# circuit.net
KiCad netlist of a schematic drawn in EAGLE
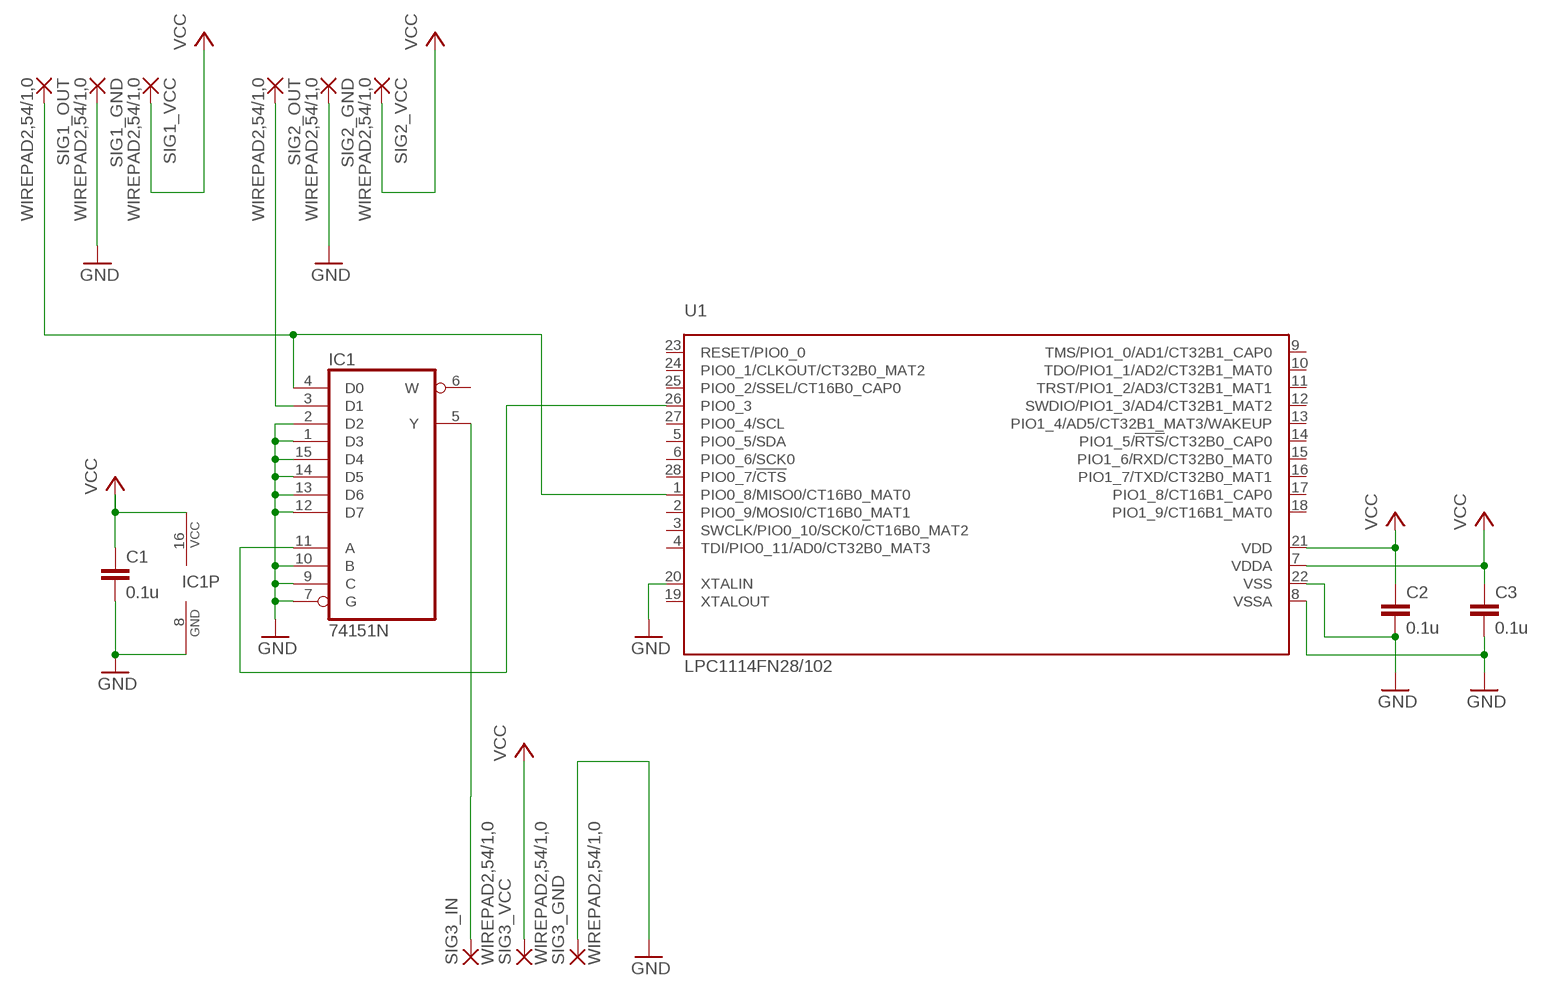
[diagram p0: schematic, sheet 1]

(export (version "E")
  (design (tool "Eeschema 10.0.6"))
  (components
    (comp (ref "C1")
      (value "0.1u")
      (footprint "eagle-import:C025-024X044")
      (libsource (lib "eagle-import") (part "C-EU025-024X044"))
    )
    (comp (ref "C2")
      (value "0.1u")
      (footprint "eagle-import:C025-024X044")
      (libsource (lib "eagle-import") (part "C-EU025-024X044"))
    )
    (comp (ref "C3")
      (value "0.1u")
      (footprint "eagle-import:C025-024X044")
      (libsource (lib "eagle-import") (part "C-EU025-024X044"))
    )
    (comp (ref "IC1")
      (value "74151N")
      (footprint "eagle-import:DIL16")
      (libsource (lib "eagle-import") (part "74151N"))
    )
    (comp (ref "SIG1_GND")
      (value "WIREPAD2,54/1,0")
      (footprint "eagle-import:2,54_1,0")
      (libsource (lib "eagle-import") (part "WIREPAD2,54/1,0"))
    )
    (comp (ref "SIG1_OUT")
      (value "WIREPAD2,54/1,0")
      (footprint "eagle-import:2,54_1,0")
      (libsource (lib "eagle-import") (part "WIREPAD2,54/1,0"))
    )
    (comp (ref "SIG1_VCC")
      (value "WIREPAD2,54/1,0")
      (footprint "eagle-import:2,54_1,0")
      (libsource (lib "eagle-import") (part "WIREPAD2,54/1,0"))
    )
    (comp (ref "SIG2_GND")
      (value "WIREPAD2,54/1,0")
      (footprint "eagle-import:2,54_1,0")
      (libsource (lib "eagle-import") (part "WIREPAD2,54/1,0"))
    )
    (comp (ref "SIG2_OUT")
      (value "WIREPAD2,54/1,0")
      (footprint "eagle-import:2,54_1,0")
      (libsource (lib "eagle-import") (part "WIREPAD2,54/1,0"))
    )
    (comp (ref "SIG2_VCC")
      (value "WIREPAD2,54/1,0")
      (footprint "eagle-import:2,54_1,0")
      (libsource (lib "eagle-import") (part "WIREPAD2,54/1,0"))
    )
    (comp (ref "SIG3_GND")
      (value "WIREPAD2,54/1,0")
      (footprint "eagle-import:2,54_1,0")
      (libsource (lib "eagle-import") (part "WIREPAD2,54/1,0"))
    )
    (comp (ref "SIG3_IN")
      (value "WIREPAD2,54/1,0")
      (footprint "eagle-import:2,54_1,0")
      (libsource (lib "eagle-import") (part "WIREPAD2,54/1,0"))
    )
    (comp (ref "SIG3_VCC")
      (value "WIREPAD2,54/1,0")
      (footprint "eagle-import:2,54_1,0")
      (libsource (lib "eagle-import") (part "WIREPAD2,54/1,0"))
    )
    (comp (ref "U1")
      (value "LPC1114FN28/102")
      (footprint "eagle-import:SOT117")
      (libsource (lib "eagle-import") (part "LPC1114FN28/102"))
    )
  )
  (nets
    (net (code "1") (name "GND") (class "Default")
      (node (ref "C1") (pin "2") (pinfunction "2_2") (pintype "passive"))
      (node (ref "C2") (pin "2") (pinfunction "2_2") (pintype "passive"))
      (node (ref "C3") (pin "2") (pinfunction "2_2") (pintype "passive"))
      (node (ref "IC1") (pin "1") (pinfunction "D3_1") (pintype "input"))
      (node (ref "IC1") (pin "10") (pinfunction "B_10") (pintype "input"))
      (node (ref "IC1") (pin "12") (pinfunction "D7_12") (pintype "input"))
      (node (ref "IC1") (pin "13") (pinfunction "D6_13") (pintype "input"))
      (node (ref "IC1") (pin "14") (pinfunction "D5_14") (pintype "input"))
      (node (ref "IC1") (pin "15") (pinfunction "D4_15") (pintype "input"))
      (node (ref "IC1") (pin "2") (pinfunction "D2_2") (pintype "input"))
      (node (ref "IC1") (pin "7") (pinfunction "G_7") (pintype "input"))
      (node (ref "IC1") (pin "8") (pinfunction "GND_8") (pintype "power_in"))
      (node (ref "IC1") (pin "9") (pinfunction "C_9") (pintype "input"))
      (node (ref "SIG1_GND") (pin "1") (pinfunction "P_1") (pintype "passive"))
      (node (ref "SIG2_GND") (pin "1") (pinfunction "P_1") (pintype "passive"))
      (node (ref "SIG3_GND") (pin "1") (pinfunction "P_1") (pintype "passive"))
      (node (ref "U1") (pin "20") (pinfunction "XTALIN_20") (pintype "input"))
      (node (ref "U1") (pin "22") (pinfunction "VSS_22") (pintype "power_in"))
      (node (ref "U1") (pin "8") (pinfunction "VSSA_8") (pintype "power_in"))
    )
    (net (code "2") (name "Net-(IC1A-A)") (class "Default")
      (node (ref "IC1") (pin "11") (pinfunction "A_11") (pintype "input"))
      (node (ref "U1") (pin "26") (pinfunction "PIO0_3_26") (pintype "bidirectional"))
    )
    (net (code "3") (name "Net-(IC1A-D0)") (class "Default")
      (node (ref "IC1") (pin "4") (pinfunction "D0_4") (pintype "input"))
      (node (ref "SIG1_OUT") (pin "1") (pinfunction "P_1") (pintype "passive"))
      (node (ref "U1") (pin "1") (pinfunction "PIO0_8/MISO0/CT16B0_MAT0_1") (pintype "bidirectional"))
    )
    (net (code "4") (name "Net-(IC1A-D1)") (class "Default")
      (node (ref "IC1") (pin "3") (pinfunction "D1_3") (pintype "input"))
      (node (ref "SIG2_OUT") (pin "1") (pinfunction "P_1") (pintype "passive"))
    )
    (net (code "5") (name "Net-(IC1A-Y)") (class "Default")
      (node (ref "IC1") (pin "5") (pinfunction "Y_5") (pintype "output"))
      (node (ref "SIG3_IN") (pin "1") (pinfunction "P_1") (pintype "passive"))
    )
    (net (code "6") (name "VCC") (class "Default")
      (node (ref "C1") (pin "1") (pinfunction "1_1") (pintype "passive"))
      (node (ref "C2") (pin "1") (pinfunction "1_1") (pintype "passive"))
      (node (ref "C3") (pin "1") (pinfunction "1_1") (pintype "passive"))
      (node (ref "IC1") (pin "16") (pinfunction "VCC_16") (pintype "power_in"))
      (node (ref "SIG1_VCC") (pin "1") (pinfunction "P_1") (pintype "passive"))
      (node (ref "SIG2_VCC") (pin "1") (pinfunction "P_1") (pintype "passive"))
      (node (ref "SIG3_VCC") (pin "1") (pinfunction "P_1") (pintype "passive"))
      (node (ref "U1") (pin "21") (pinfunction "VDD_21") (pintype "power_in"))
      (node (ref "U1") (pin "7") (pinfunction "VDDA_7") (pintype "power_in"))
    )
    (net (code "7") (name "unconnected-(IC1A-W-Pad6)") (class "Default")
      (node (ref "IC1") (pin "6") (pinfunction "W_6") (pintype "output"))
    )
    (net (code "8") (name "unconnected-(U1-PIO0_1{slash}CLKOUT{slash}CT32B0_MAT2-Pad24)") (class "Default")
      (node (ref "U1") (pin "24") (pinfunction "PIO0_1/CLKOUT/CT32B0_MAT2_24") (pintype "bidirectional"))
    )
    (net (code "9") (name "unconnected-(U1-PIO0_2{slash}SSEL{slash}CT16B0_CAP0-Pad25)") (class "Default")
      (node (ref "U1") (pin "25") (pinfunction "PIO0_2/SSEL/CT16B0_CAP0_25") (pintype "bidirectional"))
    )
    (net (code "10") (name "unconnected-(U1-PIO0_4{slash}SCL-Pad27)") (class "Default")
      (node (ref "U1") (pin "27") (pinfunction "PIO0_4/SCL_27") (pintype "bidirectional"))
    )
    (net (code "11") (name "unconnected-(U1-PIO0_5{slash}SDA-Pad5)") (class "Default")
      (node (ref "U1") (pin "5") (pinfunction "PIO0_5/SDA_5") (pintype "bidirectional"))
    )
    (net (code "12") (name "unconnected-(U1-PIO0_6{slash}SCK0-Pad6)") (class "Default")
      (node (ref "U1") (pin "6") (pinfunction "PIO0_6/SCK0_6") (pintype "bidirectional"))
    )
    (net (code "13") (name "unconnected-(U1-PIO0_7{slash}~{CTS}-Pad28)") (class "Default")
      (node (ref "U1") (pin "28") (pinfunction "PIO0_7/~{CTS}_28") (pintype "bidirectional"))
    )
    (net (code "14") (name "unconnected-(U1-PIO0_9{slash}MOSI0{slash}CT16B0_MAT1-Pad2)") (class "Default")
      (node (ref "U1") (pin "2") (pinfunction "PIO0_9/MOSI0/CT16B0_MAT1_2") (pintype "bidirectional"))
    )
    (net (code "15") (name "unconnected-(U1-PIO1_4{slash}AD5{slash}CT32B1_MAT3{slash}WAKEUP-Pad13)") (class "Default")
      (node (ref "U1") (pin "13") (pinfunction "PIO1_4/AD5/CT32B1_MAT3/WAKEUP_13") (pintype "bidirectional"))
    )
    (net (code "16") (name "unconnected-(U1-PIO1_5{slash}~{RTS}{slash}CT32B0_CAP0-Pad14)") (class "Default")
      (node (ref "U1") (pin "14") (pinfunction "PIO1_5/~{RTS}/CT32B0_CAP0_14") (pintype "bidirectional"))
    )
    (net (code "17") (name "unconnected-(U1-PIO1_6{slash}RXD{slash}CT32B0_MAT0-Pad15)") (class "Default")
      (node (ref "U1") (pin "15") (pinfunction "PIO1_6/RXD/CT32B0_MAT0_15") (pintype "bidirectional"))
    )
    (net (code "18") (name "unconnected-(U1-PIO1_7{slash}TXD{slash}CT32B0_MAT1-Pad16)") (class "Default")
      (node (ref "U1") (pin "16") (pinfunction "PIO1_7/TXD/CT32B0_MAT1_16") (pintype "bidirectional"))
    )
    (net (code "19") (name "unconnected-(U1-PIO1_8{slash}CT16B1_CAP0-Pad17)") (class "Default")
      (node (ref "U1") (pin "17") (pinfunction "PIO1_8/CT16B1_CAP0_17") (pintype "bidirectional"))
    )
    (net (code "20") (name "unconnected-(U1-PIO1_9{slash}CT16B1_MAT0-Pad18)") (class "Default")
      (node (ref "U1") (pin "18") (pinfunction "PIO1_9/CT16B1_MAT0_18") (pintype "bidirectional"))
    )
    (net (code "21") (name "unconnected-(U1-RESET{slash}PIO0_0-Pad23)") (class "Default")
      (node (ref "U1") (pin "23") (pinfunction "RESET/PIO0_0_23") (pintype "bidirectional"))
    )
    (net (code "22") (name "unconnected-(U1-SWCLK{slash}PIO0_10{slash}SCK0{slash}CT16B0_MAT2-Pad3)") (class "Default")
      (node (ref "U1") (pin "3") (pinfunction "SWCLK/PIO0_10/SCK0/CT16B0_MAT2_3") (pintype "bidirectional"))
    )
    (net (code "23") (name "unconnected-(U1-SWDIO{slash}PIO1_3{slash}AD4{slash}CT32B1_MAT2-Pad12)") (class "Default")
      (node (ref "U1") (pin "12") (pinfunction "SWDIO/PIO1_3/AD4/CT32B1_MAT2_12") (pintype "bidirectional"))
    )
    (net (code "24") (name "unconnected-(U1-TDI{slash}PIO0_11{slash}AD0{slash}CT32B0_MAT3-Pad4)") (class "Default")
      (node (ref "U1") (pin "4") (pinfunction "TDI/PIO0_11/AD0/CT32B0_MAT3_4") (pintype "bidirectional"))
    )
    (net (code "25") (name "unconnected-(U1-TDO{slash}PIO1_1{slash}AD2{slash}CT32B1_MAT0-Pad10)") (class "Default")
      (node (ref "U1") (pin "10") (pinfunction "TDO/PIO1_1/AD2/CT32B1_MAT0_10") (pintype "bidirectional"))
    )
    (net (code "26") (name "unconnected-(U1-TMS{slash}PIO1_0{slash}AD1{slash}CT32B1_CAP0-Pad9)") (class "Default")
      (node (ref "U1") (pin "9") (pinfunction "TMS/PIO1_0/AD1/CT32B1_CAP0_9") (pintype "bidirectional"))
    )
    (net (code "27") (name "unconnected-(U1-TRST{slash}PIO1_2{slash}AD3{slash}CT32B1_MAT1-Pad11)") (class "Default")
      (node (ref "U1") (pin "11") (pinfunction "TRST/PIO1_2/AD3/CT32B1_MAT1_11") (pintype "bidirectional"))
    )
    (net (code "28") (name "unconnected-(U1-XTALOUT-Pad19)") (class "Default")
      (node (ref "U1") (pin "19") (pinfunction "XTALOUT_19") (pintype "output"))
    )
  )
)
